# tritag.net
KiCad netlist of a schematic drawn in EAGLE
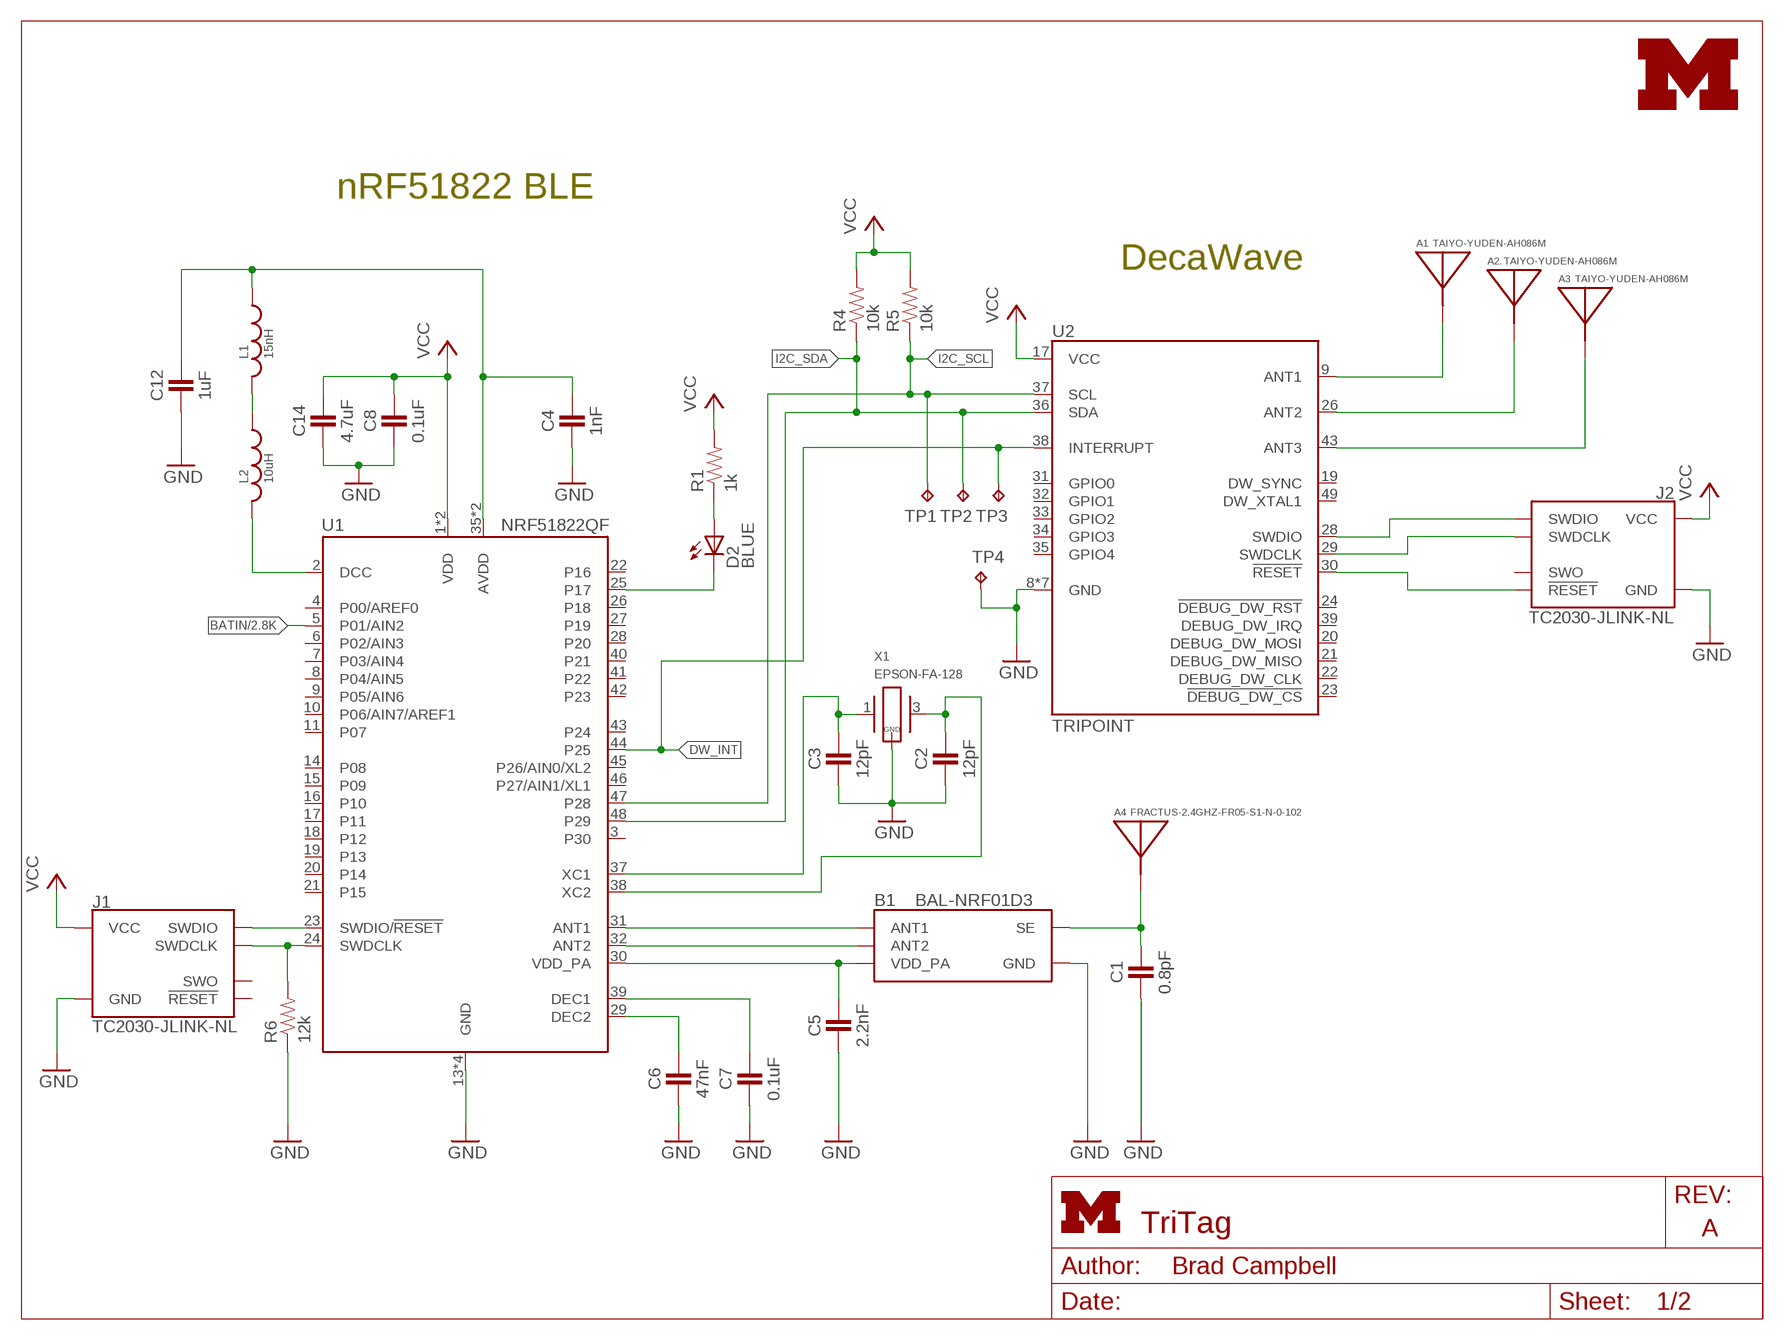
[diagram p0: schematic, sheet 1]
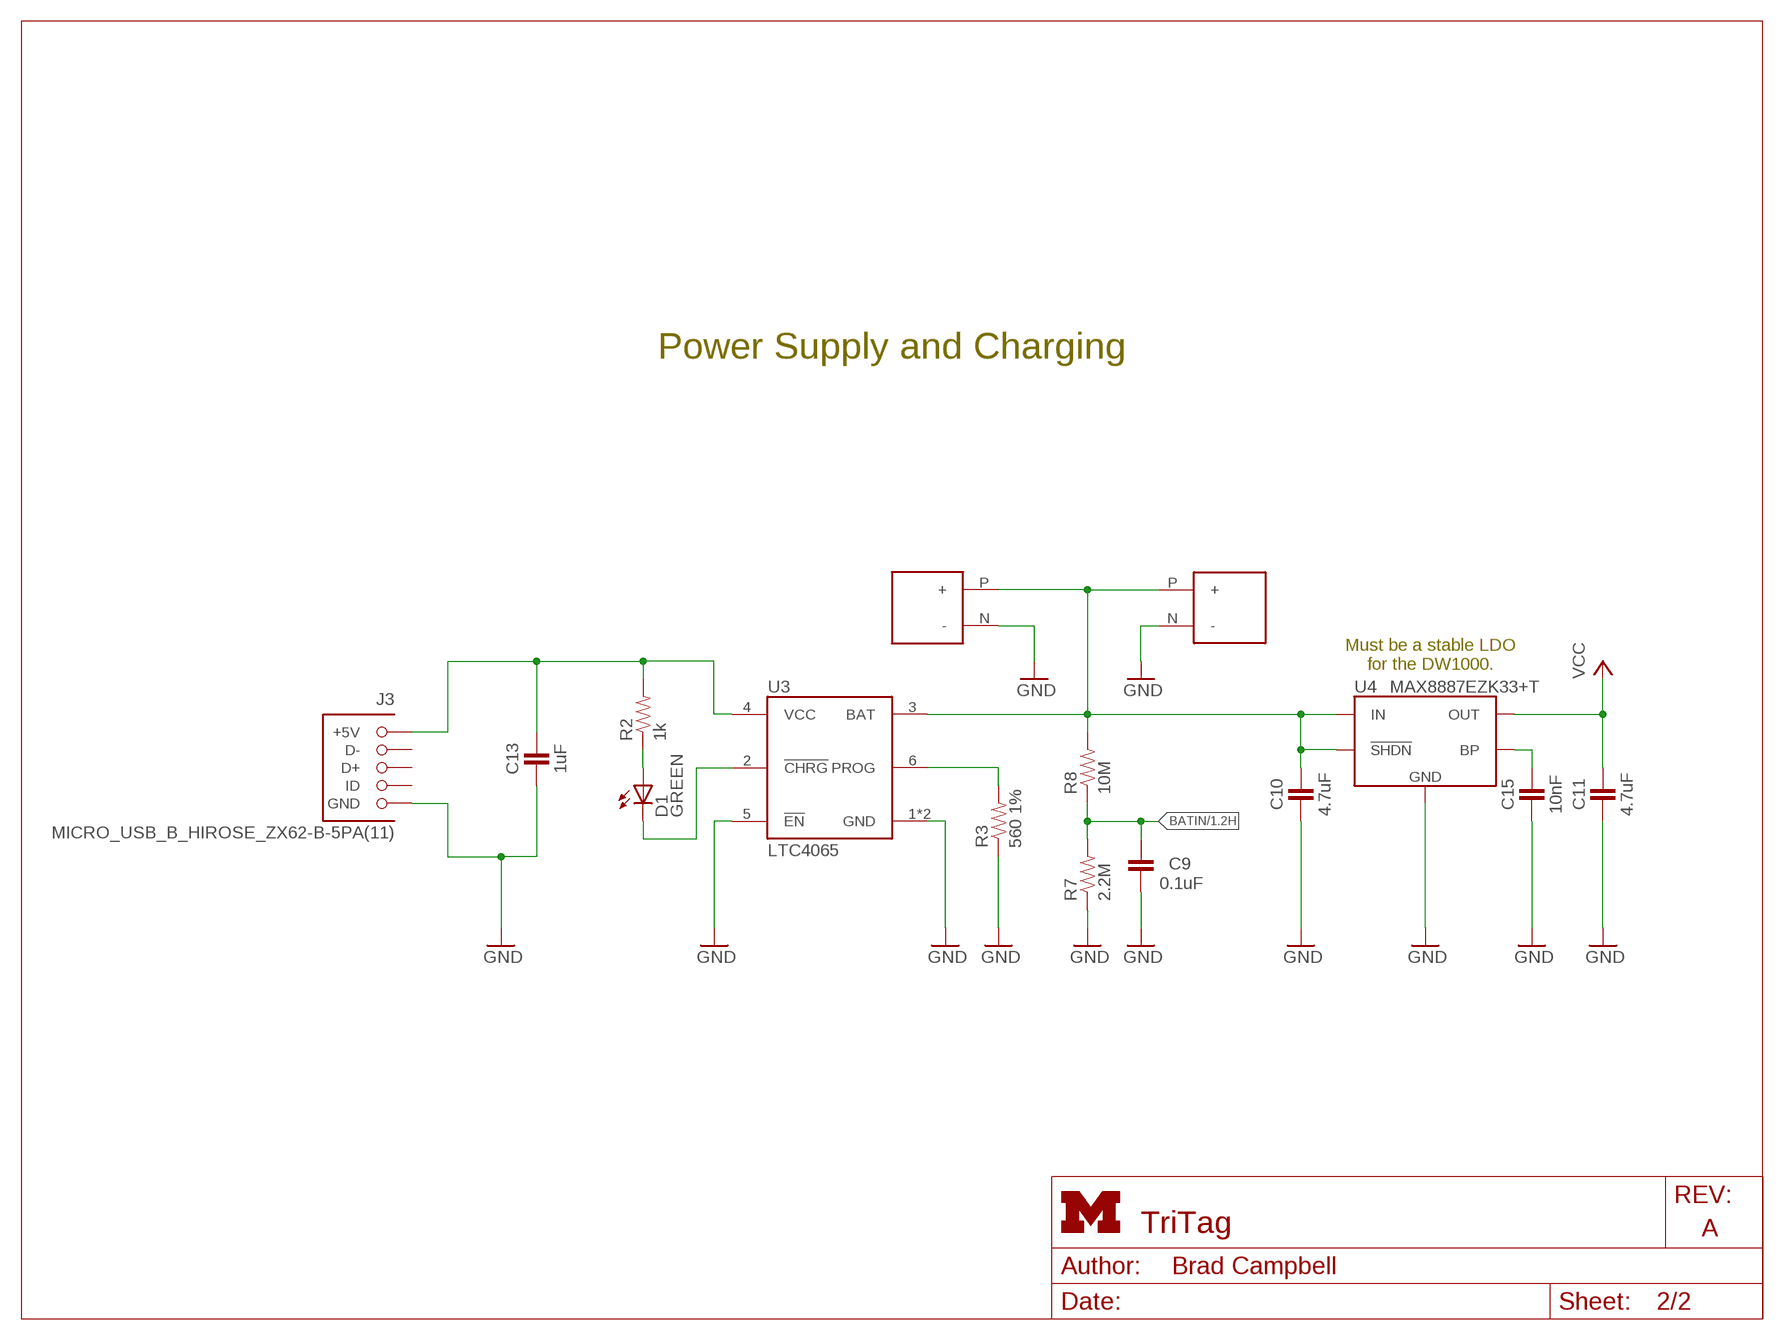
[diagram p1: schematic, sheet 2]

(export (version "E")
  (design (tool "Eeschema 10.0.6"))
  (components
    (comp (ref "C9")
      (value "0.1uF")
      (footprint "eagle-import:0402_CAP")
      (libsource (lib "eagle-import") (part "CAPACITOR"))
    )
    (comp (ref "C10")
      (value "4.7uF")
      (footprint "eagle-import:0402_CAP")
      (libsource (lib "eagle-import") (part "CAPACITOR"))
    )
    (comp (ref "C11")
      (value "4.7uF")
      (footprint "eagle-import:0402_CAP")
      (libsource (lib "eagle-import") (part "CAPACITOR"))
    )
    (comp (ref "C13")
      (value "1uF")
      (footprint "eagle-import:0402_CAP")
      (libsource (lib "eagle-import") (part "CAPACITOR"))
    )
    (comp (ref "C15")
      (value "10nF")
      (footprint "eagle-import:0402_CAP")
      (libsource (lib "eagle-import") (part "CAPACITOR"))
    )
    (comp (ref "D1")
      (value "GREEN")
      (footprint "eagle-import:LED-0603")
      (libsource (lib "eagle-import") (part "LED0603"))
    )
    (comp (ref "J3")
      (value "MICRO_USB_B_HIROSE_ZX62-B-5PA(11)")
      (footprint "eagle-import:USB_MICRO_B-HIROSE-ZX62-B-5PA(11)")
      (libsource (lib "eagle-import") (part "MICRO_USB_B_HIROSE_ZX62-B-5PA(11)"))
    )
    (comp (ref "J4")
      (value "BAT_HOLE")
      (footprint "eagle-import:BATTERY_HOLE")
      (libsource (lib "eagle-import") (part "BAT_HOLE"))
    )
    (comp (ref "J5")
      (value "BAT_HOLE")
      (footprint "eagle-import:BATTERY_HOLE")
      (libsource (lib "eagle-import") (part "BAT_HOLE"))
    )
    (comp (ref "R2")
      (value "1k")
      (footprint "eagle-import:0402_RES")
      (libsource (lib "eagle-import") (part "RESISTOR0402_RES"))
    )
    (comp (ref "R3")
      (value "560 1%")
      (footprint "eagle-import:0402_RES")
      (libsource (lib "eagle-import") (part "RESISTOR0402_RES"))
    )
    (comp (ref "R7")
      (value "2.2M")
      (footprint "eagle-import:0402_RES")
      (libsource (lib "eagle-import") (part "RESISTOR0402_RES"))
    )
    (comp (ref "R8")
      (value "10M")
      (footprint "eagle-import:0402_RES")
      (libsource (lib "eagle-import") (part "RESISTOR0402_RES"))
    )
    (comp (ref "U3")
      (value "LTC4065")
      (footprint "eagle-import:DFN-6_2MM")
      (libsource (lib "eagle-import") (part "LTC4065"))
    )
    (comp (ref "U4")
      (value "MAX8887EZK33+T")
      (footprint "eagle-import:SOT-23-5")
      (libsource (lib "eagle-import") (part "MAX8887EZK33+T"))
    )
    (comp (ref "A1")
      (value "TAIYO-YUDEN-AH086M")
      (footprint "eagle-import:TAIYO-YUDEN-AH086M")
      (libsource (lib "eagle-import") (part "TAIYO-YUDEN-AH086M"))
    )
    (comp (ref "A2.")
      (value "TAIYO-YUDEN-AH086M")
      (footprint "eagle-import:TAIYO-YUDEN-AH086M")
      (libsource (lib "eagle-import") (part "TAIYO-YUDEN-AH086M"))
    )
    (comp (ref "A3")
      (value "TAIYO-YUDEN-AH086M")
      (footprint "eagle-import:TAIYO-YUDEN-AH086M")
      (libsource (lib "eagle-import") (part "TAIYO-YUDEN-AH086M"))
    )
    (comp (ref "A4")
      (value "FRACTUS-2.4GHZ-FR05-S1-N-0-102")
      (footprint "eagle-import:FRACTUS-ANTENNA-FR05-S1-N-0-102")
      (libsource (lib "eagle-import") (part "FRACTUS-2.4GHZ-FR05-S1-N-0-102"))
    )
    (comp (ref "B1")
      (value "BAL-NRF01D3")
      (footprint "eagle-import:BAL-NRF01D3")
      (libsource (lib "eagle-import") (part "BAL-NRF01D3"))
    )
    (comp (ref "C1")
      (value "0.8pF")
      (footprint "eagle-import:0402_CAP")
      (libsource (lib "eagle-import") (part "CAPACITOR"))
    )
    (comp (ref "C2")
      (value "12pF")
      (footprint "eagle-import:0402_CAP")
      (libsource (lib "eagle-import") (part "CAPACITOR"))
    )
    (comp (ref "C3")
      (value "12pF")
      (footprint "eagle-import:0402_CAP")
      (libsource (lib "eagle-import") (part "CAPACITOR"))
    )
    (comp (ref "C4")
      (value "1nF")
      (footprint "eagle-import:0402_CAP")
      (libsource (lib "eagle-import") (part "CAPACITOR"))
    )
    (comp (ref "C5")
      (value "2.2nF")
      (footprint "eagle-import:0402_CAP")
      (libsource (lib "eagle-import") (part "CAPACITOR"))
    )
    (comp (ref "C6")
      (value "47nF")
      (footprint "eagle-import:0402_CAP")
      (libsource (lib "eagle-import") (part "CAPACITOR"))
    )
    (comp (ref "C7")
      (value "0.1uF")
      (footprint "eagle-import:0402_CAP")
      (libsource (lib "eagle-import") (part "CAPACITOR"))
    )
    (comp (ref "C8")
      (value "0.1uF")
      (footprint "eagle-import:0402_CAP")
      (libsource (lib "eagle-import") (part "CAPACITOR"))
    )
    (comp (ref "C12")
      (value "1uF")
      (footprint "eagle-import:0402_CAP")
      (libsource (lib "eagle-import") (part "CAPACITOR"))
    )
    (comp (ref "C14")
      (value "4.7uF")
      (footprint "eagle-import:0402_CAP")
      (libsource (lib "eagle-import") (part "CAPACITOR"))
    )
    (comp (ref "D2")
      (value "BLUE")
      (footprint "eagle-import:LED-0603")
      (libsource (lib "eagle-import") (part "LED0603"))
    )
    (comp (ref "J1")
      (value "TC2030-JLINK-NL")
      (footprint "eagle-import:TC2030-IDC-NL")
      (libsource (lib "eagle-import") (part "TC2030-JLINK-NL"))
    )
    (comp (ref "J2")
      (value "TC2030-JLINK-NL")
      (footprint "eagle-import:TC2030-IDC-NL")
      (libsource (lib "eagle-import") (part "TC2030-JLINK-NL"))
    )
    (comp (ref "L1")
      (value "15nH")
      (footprint "eagle-import:0402_CAP")
      (libsource (lib "eagle-import") (part "INDUCTOR0402"))
    )
    (comp (ref "L2")
      (value "10uH")
      (footprint "eagle-import:0603_CAP")
      (libsource (lib "eagle-import") (part "INDUCTOR0603"))
    )
    (comp (ref "LOGO1")
      (value "UMICH_SOLID_SMALL")
      (footprint "eagle-import:UMICH_SOLID_75MIL")
      (libsource (lib "eagle-import") (part "UMICH_SOLID_SMALL"))
    )
    (comp (ref "R1")
      (value "1k")
      (footprint "eagle-import:0402_RES")
      (libsource (lib "eagle-import") (part "RESISTOR0402_RES"))
    )
    (comp (ref "R4")
      (value "10k")
      (footprint "eagle-import:0402_RES")
      (libsource (lib "eagle-import") (part "RESISTOR0402_RES"))
    )
    (comp (ref "R5")
      (value "10k")
      (footprint "eagle-import:0402_RES")
      (libsource (lib "eagle-import") (part "RESISTOR0402_RES"))
    )
    (comp (ref "R6")
      (value "12k")
      (footprint "eagle-import:0402_RES")
      (libsource (lib "eagle-import") (part "RESISTOR0402_RES"))
    )
    (comp (ref "TP1")
      (value "TPTP06SQ")
      (footprint "eagle-import:TP06SQ")
      (libsource (lib "eagle-import") (part "TPTP06SQ"))
    )
    (comp (ref "TP2")
      (value "TPTP06SQ")
      (footprint "eagle-import:TP06SQ")
      (libsource (lib "eagle-import") (part "TPTP06SQ"))
    )
    (comp (ref "TP3")
      (value "TPTP06SQ")
      (footprint "eagle-import:TP06SQ")
      (libsource (lib "eagle-import") (part "TPTP06SQ"))
    )
    (comp (ref "TP4")
      (value "TPTP06SQ")
      (footprint "eagle-import:TP06SQ")
      (libsource (lib "eagle-import") (part "TPTP06SQ"))
    )
    (comp (ref "U1")
      (value "NRF51822QF")
      (footprint "eagle-import:QFN-48-6MM")
      (libsource (lib "eagle-import") (part "NRF51822QF"))
    )
    (comp (ref "U2")
      (value "TRIPOINT")
      (footprint "eagle-import:TRIPOINT")
      (libsource (lib "eagle-import") (part "TRIPOINT"))
    )
    (comp (ref "X1")
      (value "EPSON-FA-128")
      (footprint "eagle-import:FA-128")
      (libsource (lib "eagle-import") (part "EPSON-FA-128"))
    )
  )
  (nets
    (net (code "1") (name "BATIN") (class "Default")
      (node (ref "C9") (pin "2") (pinfunction "2_2") (pintype "bidirectional"))
      (node (ref "R7") (pin "2") (pinfunction "2_2") (pintype "passive"))
      (node (ref "R8") (pin "1") (pinfunction "1_1") (pintype "passive"))
      (node (ref "U1") (pin "5") (pinfunction "P01/AIN2_5") (pintype "bidirectional"))
    )
    (net (code "2") (name "DW_INT") (class "Default")
      (node (ref "TP3") (pin "TP") (pinfunction "TP_TP") (pintype "input"))
      (node (ref "U1") (pin "44") (pinfunction "P25_44") (pintype "bidirectional"))
      (node (ref "U2") (pin "38") (pinfunction "INTERRUPT_38") (pintype "bidirectional"))
    )
    (net (code "3") (name "GND") (class "Default")
      (node (ref "B1") (pin "GND") (pinfunction "GND_GND") (pintype "bidirectional"))
      (node (ref "C1") (pin "2") (pinfunction "2_2") (pintype "bidirectional"))
      (node (ref "C10") (pin "2") (pinfunction "2_2") (pintype "bidirectional"))
      (node (ref "C11") (pin "2") (pinfunction "2_2") (pintype "bidirectional"))
      (node (ref "C12") (pin "2") (pinfunction "2_2") (pintype "bidirectional"))
      (node (ref "C13") (pin "2") (pinfunction "2_2") (pintype "bidirectional"))
      (node (ref "C14") (pin "2") (pinfunction "2_2") (pintype "bidirectional"))
      (node (ref "C15") (pin "2") (pinfunction "2_2") (pintype "bidirectional"))
      (node (ref "C2") (pin "2") (pinfunction "2_2") (pintype "bidirectional"))
      (node (ref "C3") (pin "2") (pinfunction "2_2") (pintype "bidirectional"))
      (node (ref "C4") (pin "2") (pinfunction "2_2") (pintype "bidirectional"))
      (node (ref "C5") (pin "2") (pinfunction "2_2") (pintype "bidirectional"))
      (node (ref "C6") (pin "2") (pinfunction "2_2") (pintype "bidirectional"))
      (node (ref "C7") (pin "2") (pinfunction "2_2") (pintype "bidirectional"))
      (node (ref "C8") (pin "2") (pinfunction "2_2") (pintype "bidirectional"))
      (node (ref "C9") (pin "1") (pinfunction "1_1") (pintype "bidirectional"))
      (node (ref "J1") (pin "5") (pinfunction "GND_5") (pintype "bidirectional"))
      (node (ref "J2") (pin "5") (pinfunction "GND_5") (pintype "bidirectional"))
      (node (ref "J3") (pin "5") (pinfunction "GND_5") (pintype "bidirectional"))
      (node (ref "J4") (pin "N") (pinfunction "-_N") (pintype "bidirectional"))
      (node (ref "J5") (pin "N") (pinfunction "-_N") (pintype "bidirectional"))
      (node (ref "R3") (pin "1") (pinfunction "1_1") (pintype "passive"))
      (node (ref "R6") (pin "1") (pinfunction "1_1") (pintype "passive"))
      (node (ref "R7") (pin "1") (pinfunction "1_1") (pintype "passive"))
      (node (ref "TP4") (pin "TP") (pinfunction "TP_TP") (pintype "input"))
      (node (ref "U1") (pin "13") (pinfunction "GND_13") (pintype "bidirectional"))
      (node (ref "U1") (pin "33") (pinfunction "GND_33") (pintype "bidirectional"))
      (node (ref "U1") (pin "34") (pinfunction "GND_34") (pintype "bidirectional"))
      (node (ref "U1") (pin "GND") (pinfunction "GND_GND") (pintype "bidirectional"))
      (node (ref "U2") (pin "10") (pinfunction "GND_10") (pintype "bidirectional"))
      (node (ref "U2") (pin "18") (pinfunction "GND_18") (pintype "bidirectional"))
      (node (ref "U2") (pin "25") (pinfunction "GND_25") (pintype "bidirectional"))
      (node (ref "U2") (pin "27") (pinfunction "GND_27") (pintype "bidirectional"))
      (node (ref "U2") (pin "42") (pinfunction "GND_42") (pintype "bidirectional"))
      (node (ref "U2") (pin "44") (pinfunction "GND_44") (pintype "bidirectional"))
      (node (ref "U2") (pin "8") (pinfunction "GND_8") (pintype "bidirectional"))
      (node (ref "U3") (pin "1") (pinfunction "GND_1") (pintype "bidirectional"))
      (node (ref "U3") (pin "5") (pinfunction "~{EN}_5") (pintype "bidirectional"))
      (node (ref "U3") (pin "7") (pinfunction "GND_7") (pintype "bidirectional"))
      (node (ref "U4") (pin "2") (pinfunction "GND_2") (pintype "bidirectional"))
      (node (ref "X1") (pin "2") (pinfunction "GND_2") (pintype "bidirectional"))
      (node (ref "X1") (pin "4") (pinfunction "GND_4") (pintype "bidirectional"))
    )
    (net (code "4") (name "I2C_SCL") (class "Default")
      (node (ref "R5") (pin "1") (pinfunction "1_1") (pintype "passive"))
      (node (ref "TP1") (pin "TP") (pinfunction "TP_TP") (pintype "input"))
      (node (ref "U1") (pin "47") (pinfunction "P28_47") (pintype "bidirectional"))
      (node (ref "U2") (pin "37") (pinfunction "SCL_37") (pintype "bidirectional"))
    )
    (net (code "5") (name "I2C_SDA") (class "Default")
      (node (ref "R4") (pin "1") (pinfunction "1_1") (pintype "passive"))
      (node (ref "TP2") (pin "TP") (pinfunction "TP_TP") (pintype "input"))
      (node (ref "U1") (pin "48") (pinfunction "P29_48") (pintype "bidirectional"))
      (node (ref "U2") (pin "36") (pinfunction "SDA_36") (pintype "bidirectional"))
    )
    (net (code "6") (name "Net-(A1-ANTENNA)") (class "Default")
      (node (ref "A1") (pin "A") (pinfunction "ANTENNA_A") (pintype "bidirectional"))
      (node (ref "U2") (pin "9") (pinfunction "ANT1_9") (pintype "bidirectional"))
    )
    (net (code "7") (name "Net-(A2.-ANTENNA)") (class "Default")
      (node (ref "A2.") (pin "A") (pinfunction "ANTENNA_A") (pintype "bidirectional"))
      (node (ref "U2") (pin "26") (pinfunction "ANT2_26") (pintype "bidirectional"))
    )
    (net (code "8") (name "Net-(A3-ANTENNA)") (class "Default")
      (node (ref "A3") (pin "A") (pinfunction "ANTENNA_A") (pintype "bidirectional"))
      (node (ref "U2") (pin "43") (pinfunction "ANT3_43") (pintype "bidirectional"))
    )
    (net (code "9") (name "Net-(A4-ANTENNA)") (class "Default")
      (node (ref "A4") (pin "1") (pinfunction "ANTENNA_1") (pintype "bidirectional"))
      (node (ref "B1") (pin "SE") (pinfunction "SE_SE") (pintype "bidirectional"))
      (node (ref "C1") (pin "1") (pinfunction "1_1") (pintype "bidirectional"))
    )
    (net (code "10") (name "Net-(B1-VDD_PA)") (class "Default")
      (node (ref "B1") (pin "VCC") (pinfunction "VDD_PA_VCC") (pintype "bidirectional"))
      (node (ref "C5") (pin "1") (pinfunction "1_1") (pintype "bidirectional"))
      (node (ref "U1") (pin "30") (pinfunction "VDD_PA_30") (pintype "bidirectional"))
    )
    (net (code "11") (name "Net-(C12-Pad1)") (class "Default")
      (node (ref "C12") (pin "1") (pinfunction "1_1") (pintype "bidirectional"))
      (node (ref "C4") (pin "1") (pinfunction "1_1") (pintype "bidirectional"))
      (node (ref "L1") (pin "1") (pinfunction "1_1") (pintype "bidirectional"))
      (node (ref "U1") (pin "35") (pinfunction "AVDD_35") (pintype "bidirectional"))
      (node (ref "U1") (pin "36") (pinfunction "AVDD_36") (pintype "bidirectional"))
    )
    (net (code "12") (name "Net-(D1-PadA)") (class "Default")
      (node (ref "D1") (pin "A") (pinfunction "A_A") (pintype "passive"))
      (node (ref "R2") (pin "1") (pinfunction "1_1") (pintype "passive"))
    )
    (net (code "13") (name "Net-(D2-PadA)") (class "Default")
      (node (ref "D2") (pin "A") (pinfunction "A_A") (pintype "passive"))
      (node (ref "R1") (pin "1") (pinfunction "1_1") (pintype "passive"))
    )
    (net (code "14") (name "Net-(J1-SWDCLK)") (class "Default")
      (node (ref "J1") (pin "4") (pinfunction "SWDCLK_4") (pintype "bidirectional"))
      (node (ref "R6") (pin "2") (pinfunction "2_2") (pintype "passive"))
      (node (ref "U1") (pin "24") (pinfunction "SWDCLK_24") (pintype "bidirectional"))
    )
    (net (code "15") (name "Net-(J1-SWDIO)") (class "Default")
      (node (ref "J1") (pin "2") (pinfunction "SWDIO_2") (pintype "bidirectional"))
      (node (ref "U1") (pin "23") (pinfunction "SWDIO/~{RESET}_23") (pintype "bidirectional"))
    )
    (net (code "16") (name "Net-(J2-SWDCLK)") (class "Default")
      (node (ref "J2") (pin "4") (pinfunction "SWDCLK_4") (pintype "bidirectional"))
      (node (ref "U2") (pin "29") (pinfunction "SWDCLK_29") (pintype "bidirectional"))
    )
    (net (code "17") (name "Net-(J2-SWDIO)") (class "Default")
      (node (ref "J2") (pin "2") (pinfunction "SWDIO_2") (pintype "bidirectional"))
      (node (ref "U2") (pin "28") (pinfunction "SWDIO_28") (pintype "bidirectional"))
    )
    (net (code "18") (name "Net-(J2-~{RESET})") (class "Default")
      (node (ref "J2") (pin "3") (pinfunction "~{RESET}_3") (pintype "bidirectional"))
      (node (ref "U2") (pin "30") (pinfunction "~{RESET}_30") (pintype "bidirectional"))
    )
    (net (code "19") (name "Net-(J3-+5V)") (class "Default")
      (node (ref "C13") (pin "1") (pinfunction "1_1") (pintype "bidirectional"))
      (node (ref "J3") (pin "1") (pinfunction "+5V_1") (pintype "bidirectional"))
      (node (ref "R2") (pin "2") (pinfunction "2_2") (pintype "passive"))
      (node (ref "U3") (pin "4") (pinfunction "VCC_4") (pintype "bidirectional"))
    )
    (net (code "20") (name "Net-(J4-+)") (class "Default")
      (node (ref "C10") (pin "1") (pinfunction "1_1") (pintype "bidirectional"))
      (node (ref "J4") (pin "P") (pinfunction "+_P") (pintype "bidirectional"))
      (node (ref "J5") (pin "P") (pinfunction "+_P") (pintype "bidirectional"))
      (node (ref "R8") (pin "2") (pinfunction "2_2") (pintype "passive"))
      (node (ref "U3") (pin "3") (pinfunction "BAT_3") (pintype "bidirectional"))
      (node (ref "U4") (pin "1") (pinfunction "IN_1") (pintype "bidirectional"))
      (node (ref "U4") (pin "3") (pinfunction "~{SHDN}_3") (pintype "bidirectional"))
    )
    (net (code "21") (name "Net-(L1-Pad2)") (class "Default")
      (node (ref "L1") (pin "2") (pinfunction "2_2") (pintype "bidirectional"))
      (node (ref "L2") (pin "1") (pinfunction "1_1") (pintype "bidirectional"))
    )
    (net (code "22") (name "Net-(U1-ANT1)") (class "Default")
      (node (ref "B1") (pin "ANT1") (pinfunction "ANT1_ANT1") (pintype "bidirectional"))
      (node (ref "U1") (pin "31") (pinfunction "ANT1_31") (pintype "bidirectional"))
    )
    (net (code "23") (name "Net-(U1-ANT2)") (class "Default")
      (node (ref "B1") (pin "ANT2") (pinfunction "ANT2_ANT2") (pintype "bidirectional"))
      (node (ref "U1") (pin "32") (pinfunction "ANT2_32") (pintype "bidirectional"))
    )
    (net (code "24") (name "Net-(U1-DCC)") (class "Default")
      (node (ref "L2") (pin "2") (pinfunction "2_2") (pintype "bidirectional"))
      (node (ref "U1") (pin "2") (pinfunction "DCC_2") (pintype "bidirectional"))
    )
    (net (code "25") (name "Net-(U1-DEC1)") (class "Default")
      (node (ref "C7") (pin "1") (pinfunction "1_1") (pintype "bidirectional"))
      (node (ref "U1") (pin "39") (pinfunction "DEC1_39") (pintype "bidirectional"))
    )
    (net (code "26") (name "Net-(U1-DEC2)") (class "Default")
      (node (ref "C6") (pin "1") (pinfunction "1_1") (pintype "bidirectional"))
      (node (ref "U1") (pin "29") (pinfunction "DEC2_29") (pintype "bidirectional"))
    )
    (net (code "27") (name "Net-(U1-P17)") (class "Default")
      (node (ref "D2") (pin "C") (pinfunction "C_C") (pintype "passive"))
      (node (ref "U1") (pin "25") (pinfunction "P17_25") (pintype "bidirectional"))
    )
    (net (code "28") (name "Net-(U1-XC1)") (class "Default")
      (node (ref "C3") (pin "1") (pinfunction "1_1") (pintype "bidirectional"))
      (node (ref "U1") (pin "37") (pinfunction "XC1_37") (pintype "bidirectional"))
      (node (ref "X1") (pin "1") (pinfunction "1_1") (pintype "bidirectional"))
    )
    (net (code "29") (name "Net-(U1-XC2)") (class "Default")
      (node (ref "C2") (pin "1") (pinfunction "1_1") (pintype "bidirectional"))
      (node (ref "U1") (pin "38") (pinfunction "XC2_38") (pintype "bidirectional"))
      (node (ref "X1") (pin "3") (pinfunction "2_3") (pintype "bidirectional"))
    )
    (net (code "30") (name "Net-(U3-PROG)") (class "Default")
      (node (ref "R3") (pin "2") (pinfunction "2_2") (pintype "passive"))
      (node (ref "U3") (pin "6") (pinfunction "PROG_6") (pintype "bidirectional"))
    )
    (net (code "31") (name "Net-(U3-~{CHRG})") (class "Default")
      (node (ref "D1") (pin "C") (pinfunction "C_C") (pintype "passive"))
      (node (ref "U3") (pin "2") (pinfunction "~{CHRG}_2") (pintype "bidirectional"))
    )
    (net (code "32") (name "Net-(U4-BP)") (class "Default")
      (node (ref "C15") (pin "1") (pinfunction "1_1") (pintype "bidirectional"))
      (node (ref "U4") (pin "4") (pinfunction "BP_4") (pintype "bidirectional"))
    )
    (net (code "33") (name "VCC") (class "Default")
      (node (ref "C11") (pin "1") (pinfunction "1_1") (pintype "bidirectional"))
      (node (ref "C14") (pin "1") (pinfunction "1_1") (pintype "bidirectional"))
      (node (ref "C8") (pin "1") (pinfunction "1_1") (pintype "bidirectional"))
      (node (ref "J1") (pin "1") (pinfunction "VCC_1") (pintype "bidirectional"))
      (node (ref "J2") (pin "1") (pinfunction "VCC_1") (pintype "bidirectional"))
      (node (ref "R1") (pin "2") (pinfunction "2_2") (pintype "passive"))
      (node (ref "R4") (pin "2") (pinfunction "2_2") (pintype "passive"))
      (node (ref "R5") (pin "2") (pinfunction "2_2") (pintype "passive"))
      (node (ref "U1") (pin "1") (pinfunction "VDD_1") (pintype "bidirectional"))
      (node (ref "U1") (pin "12") (pinfunction "VDD_12") (pintype "bidirectional"))
      (node (ref "U2") (pin "17") (pinfunction "VCC_17") (pintype "bidirectional"))
      (node (ref "U4") (pin "5") (pinfunction "OUT_5") (pintype "bidirectional"))
    )
    (net (code "34") (name "unconnected-(J1-SWO-Pad6)") (class "Default")
      (node (ref "J1") (pin "6") (pinfunction "SWO_6") (pintype "bidirectional"))
    )
    (net (code "35") (name "unconnected-(J1-~{RESET}-Pad3)") (class "Default")
      (node (ref "J1") (pin "3") (pinfunction "~{RESET}_3") (pintype "bidirectional"))
    )
    (net (code "36") (name "unconnected-(J2-SWO-Pad6)") (class "Default")
      (node (ref "J2") (pin "6") (pinfunction "SWO_6") (pintype "bidirectional"))
    )
    (net (code "37") (name "unconnected-(J3-D+-Pad3)") (class "Default")
      (node (ref "J3") (pin "3") (pinfunction "D+_3") (pintype "bidirectional"))
    )
    (net (code "38") (name "unconnected-(J3-D--Pad2)") (class "Default")
      (node (ref "J3") (pin "2") (pinfunction "D-_2") (pintype "bidirectional"))
    )
    (net (code "39") (name "unconnected-(J3-ID-Pad4)") (class "Default")
      (node (ref "J3") (pin "4") (pinfunction "ID_4") (pintype "bidirectional"))
    )
    (net (code "40") (name "unconnected-(U1-P00{slash}AREF0-Pad4)") (class "Default")
      (node (ref "U1") (pin "4") (pinfunction "P00/AREF0_4") (pintype "bidirectional"))
    )
    (net (code "41") (name "unconnected-(U1-P02{slash}AIN3-Pad6)") (class "Default")
      (node (ref "U1") (pin "6") (pinfunction "P02/AIN3_6") (pintype "bidirectional"))
    )
    (net (code "42") (name "unconnected-(U1-P03{slash}AIN4-Pad7)") (class "Default")
      (node (ref "U1") (pin "7") (pinfunction "P03/AIN4_7") (pintype "bidirectional"))
    )
    (net (code "43") (name "unconnected-(U1-P04{slash}AIN5-Pad8)") (class "Default")
      (node (ref "U1") (pin "8") (pinfunction "P04/AIN5_8") (pintype "bidirectional"))
    )
    (net (code "44") (name "unconnected-(U1-P05{slash}AIN6-Pad9)") (class "Default")
      (node (ref "U1") (pin "9") (pinfunction "P05/AIN6_9") (pintype "bidirectional"))
    )
    (net (code "45") (name "unconnected-(U1-P06{slash}AIN7{slash}AREF1-Pad10)") (class "Default")
      (node (ref "U1") (pin "10") (pinfunction "P06/AIN7/AREF1_10") (pintype "bidirectional"))
    )
    (net (code "46") (name "unconnected-(U1-P07-Pad11)") (class "Default")
      (node (ref "U1") (pin "11") (pinfunction "P07_11") (pintype "bidirectional"))
    )
    (net (code "47") (name "unconnected-(U1-P08-Pad14)") (class "Default")
      (node (ref "U1") (pin "14") (pinfunction "P08_14") (pintype "bidirectional"))
    )
    (net (code "48") (name "unconnected-(U1-P09-Pad15)") (class "Default")
      (node (ref "U1") (pin "15") (pinfunction "P09_15") (pintype "bidirectional"))
    )
    (net (code "49") (name "unconnected-(U1-P10-Pad16)") (class "Default")
      (node (ref "U1") (pin "16") (pinfunction "P10_16") (pintype "bidirectional"))
    )
    (net (code "50") (name "unconnected-(U1-P11-Pad17)") (class "Default")
      (node (ref "U1") (pin "17") (pinfunction "P11_17") (pintype "bidirectional"))
    )
    (net (code "51") (name "unconnected-(U1-P12-Pad18)") (class "Default")
      (node (ref "U1") (pin "18") (pinfunction "P12_18") (pintype "bidirectional"))
    )
    (net (code "52") (name "unconnected-(U1-P13-Pad19)") (class "Default")
      (node (ref "U1") (pin "19") (pinfunction "P13_19") (pintype "bidirectional"))
    )
    (net (code "53") (name "unconnected-(U1-P14-Pad20)") (class "Default")
      (node (ref "U1") (pin "20") (pinfunction "P14_20") (pintype "bidirectional"))
    )
    (net (code "54") (name "unconnected-(U1-P15-Pad21)") (class "Default")
      (node (ref "U1") (pin "21") (pinfunction "P15_21") (pintype "bidirectional"))
    )
    (net (code "55") (name "unconnected-(U1-P16-Pad22)") (class "Default")
      (node (ref "U1") (pin "22") (pinfunction "P16_22") (pintype "bidirectional"))
    )
    (net (code "56") (name "unconnected-(U1-P18-Pad26)") (class "Default")
      (node (ref "U1") (pin "26") (pinfunction "P18_26") (pintype "bidirectional"))
    )
    (net (code "57") (name "unconnected-(U1-P19-Pad27)") (class "Default")
      (node (ref "U1") (pin "27") (pinfunction "P19_27") (pintype "bidirectional"))
    )
    (net (code "58") (name "unconnected-(U1-P20-Pad28)") (class "Default")
      (node (ref "U1") (pin "28") (pinfunction "P20_28") (pintype "bidirectional"))
    )
    (net (code "59") (name "unconnected-(U1-P21-Pad40)") (class "Default")
      (node (ref "U1") (pin "40") (pinfunction "P21_40") (pintype "bidirectional"))
    )
    (net (code "60") (name "unconnected-(U1-P22-Pad41)") (class "Default")
      (node (ref "U1") (pin "41") (pinfunction "P22_41") (pintype "bidirectional"))
    )
    (net (code "61") (name "unconnected-(U1-P23-Pad42)") (class "Default")
      (node (ref "U1") (pin "42") (pinfunction "P23_42") (pintype "bidirectional"))
    )
    (net (code "62") (name "unconnected-(U1-P24-Pad43)") (class "Default")
      (node (ref "U1") (pin "43") (pinfunction "P24_43") (pintype "bidirectional"))
    )
    (net (code "63") (name "unconnected-(U1-P26{slash}AIN0{slash}XL2-Pad45)") (class "Default")
      (node (ref "U1") (pin "45") (pinfunction "P26/AIN0/XL2_45") (pintype "bidirectional"))
    )
    (net (code "64") (name "unconnected-(U1-P27{slash}AIN1{slash}XL1-Pad46)") (class "Default")
      (node (ref "U1") (pin "46") (pinfunction "P27/AIN1/XL1_46") (pintype "bidirectional"))
    )
    (net (code "65") (name "unconnected-(U1-P30-Pad3)") (class "Default")
      (node (ref "U1") (pin "3") (pinfunction "P30_3") (pintype "bidirectional"))
    )
    (net (code "66") (name "unconnected-(U2-DEBUG_DW_CLK-Pad22)") (class "Default")
      (node (ref "U2") (pin "22") (pinfunction "DEBUG_DW_CLK_22") (pintype "bidirectional"))
    )
    (net (code "67") (name "unconnected-(U2-DEBUG_DW_IRQ-Pad39)") (class "Default")
      (node (ref "U2") (pin "39") (pinfunction "DEBUG_DW_IRQ_39") (pintype "bidirectional"))
    )
    (net (code "68") (name "unconnected-(U2-DEBUG_DW_MISO-Pad21)") (class "Default")
      (node (ref "U2") (pin "21") (pinfunction "DEBUG_DW_MISO_21") (pintype "bidirectional"))
    )
    (net (code "69") (name "unconnected-(U2-DEBUG_DW_MOSI-Pad20)") (class "Default")
      (node (ref "U2") (pin "20") (pinfunction "DEBUG_DW_MOSI_20") (pintype "bidirectional"))
    )
    (net (code "70") (name "unconnected-(U2-DW_SYNC-Pad19)") (class "Default")
      (node (ref "U2") (pin "19") (pinfunction "DW_SYNC_19") (pintype "bidirectional"))
    )
    (net (code "71") (name "unconnected-(U2-DW_XTAL1-Pad49)") (class "Default")
      (node (ref "U2") (pin "49") (pinfunction "DW_XTAL1_49") (pintype "bidirectional"))
    )
    (net (code "72") (name "unconnected-(U2-GPIO0-Pad31)") (class "Default")
      (node (ref "U2") (pin "31") (pinfunction "GPIO0_31") (pintype "bidirectional"))
    )
    (net (code "73") (name "unconnected-(U2-GPIO1-Pad32)") (class "Default")
      (node (ref "U2") (pin "32") (pinfunction "GPIO1_32") (pintype "bidirectional"))
    )
    (net (code "74") (name "unconnected-(U2-GPIO2-Pad33)") (class "Default")
      (node (ref "U2") (pin "33") (pinfunction "GPIO2_33") (pintype "bidirectional"))
    )
    (net (code "75") (name "unconnected-(U2-GPIO3-Pad34)") (class "Default")
      (node (ref "U2") (pin "34") (pinfunction "GPIO3_34") (pintype "bidirectional"))
    )
    (net (code "76") (name "unconnected-(U2-GPIO4-Pad35)") (class "Default")
      (node (ref "U2") (pin "35") (pinfunction "GPIO4_35") (pintype "bidirectional"))
    )
    (net (code "77") (name "unconnected-(U2-~{DEBUG_DW_CS}-Pad23)") (class "Default")
      (node (ref "U2") (pin "23") (pinfunction "~{DEBUG_DW_CS}_23") (pintype "bidirectional"))
    )
    (net (code "78") (name "unconnected-(U2-~{DEBUG_DW_RST}-Pad24)") (class "Default")
      (node (ref "U2") (pin "24") (pinfunction "~{DEBUG_DW_RST}_24") (pintype "bidirectional"))
    )
  )
)
